# prostownik_2k2p.net
KiCad netlist of a schematic drawn in EAGLE
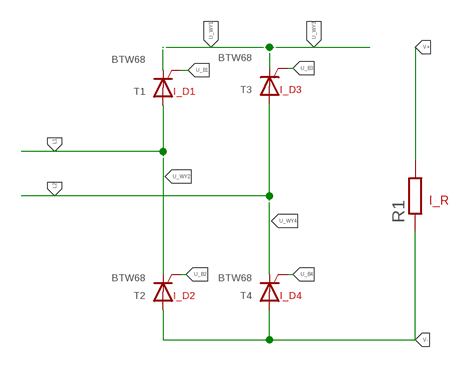
[diagram p0: schematic, sheet 1]

(export (version "E")
  (design (tool "Eeschema 10.0.6"))
  (components
    (comp (ref "R1")
      (value "R-EU_0309/12")
      (footprint "eagle-import:0309_12")
      (libsource (lib "eagle-import") (part "R-EU_0309/12"))
    )
    (comp (ref "T1")
      (value "BTW68")
      (footprint "eagle-import:TOP3S-2")
      (libsource (lib "eagle-import") (part "BTW68"))
    )
    (comp (ref "T2")
      (value "BTW68")
      (footprint "eagle-import:TOP3S-2")
      (libsource (lib "eagle-import") (part "BTW68"))
    )
    (comp (ref "T3")
      (value "BTW68")
      (footprint "eagle-import:TOP3S-2")
      (libsource (lib "eagle-import") (part "BTW68"))
    )
    (comp (ref "T4")
      (value "BTW68")
      (footprint "eagle-import:TOP3S-2")
      (libsource (lib "eagle-import") (part "BTW68"))
    )
  )
  (nets
    (net (code "1") (name "L1") (class "Default")
      (node (ref "T1") (pin "A") (pinfunction "A_A") (pintype "passive"))
    )
    (net (code "2") (name "L2") (class "Default")
      (node (ref "T3") (pin "A") (pinfunction "A_A") (pintype "passive"))
    )
    (net (code "3") (name "U_B1") (class "Default")
      (node (ref "T1") (pin "G") (pinfunction "G_G") (pintype "passive"))
    )
    (net (code "4") (name "U_B2") (class "Default")
      (node (ref "T2") (pin "G") (pinfunction "G_G") (pintype "passive"))
    )
    (net (code "5") (name "U_B3") (class "Default")
      (node (ref "T3") (pin "G") (pinfunction "G_G") (pintype "passive"))
    )
    (net (code "6") (name "U_B4") (class "Default")
      (node (ref "T4") (pin "G") (pinfunction "G_G") (pintype "passive"))
    )
    (net (code "7") (name "U_WY1") (class "Default")
      (node (ref "T1") (pin "C") (pinfunction "C_C") (pintype "passive"))
    )
    (net (code "8") (name "U_WY2") (class "Default")
      (node (ref "T2") (pin "C") (pinfunction "C_C") (pintype "passive"))
    )
    (net (code "9") (name "U_WY3") (class "Default")
      (node (ref "T3") (pin "C") (pinfunction "C_C") (pintype "passive"))
    )
    (net (code "10") (name "U_WY4") (class "Default")
      (node (ref "T4") (pin "C") (pinfunction "C_C") (pintype "passive"))
    )
    (net (code "11") (name "V+") (class "Default")
      (node (ref "R1") (pin "2") (pinfunction "2_2") (pintype "passive"))
    )
    (net (code "12") (name "V-") (class "Default")
      (node (ref "R1") (pin "1") (pinfunction "1_1") (pintype "passive"))
      (node (ref "T2") (pin "A") (pinfunction "A_A") (pintype "passive"))
      (node (ref "T4") (pin "A") (pinfunction "A_A") (pintype "passive"))
    )
  )
)
